# 8-MC_v01.net
KiCad netlist of a schematic drawn in EAGLE
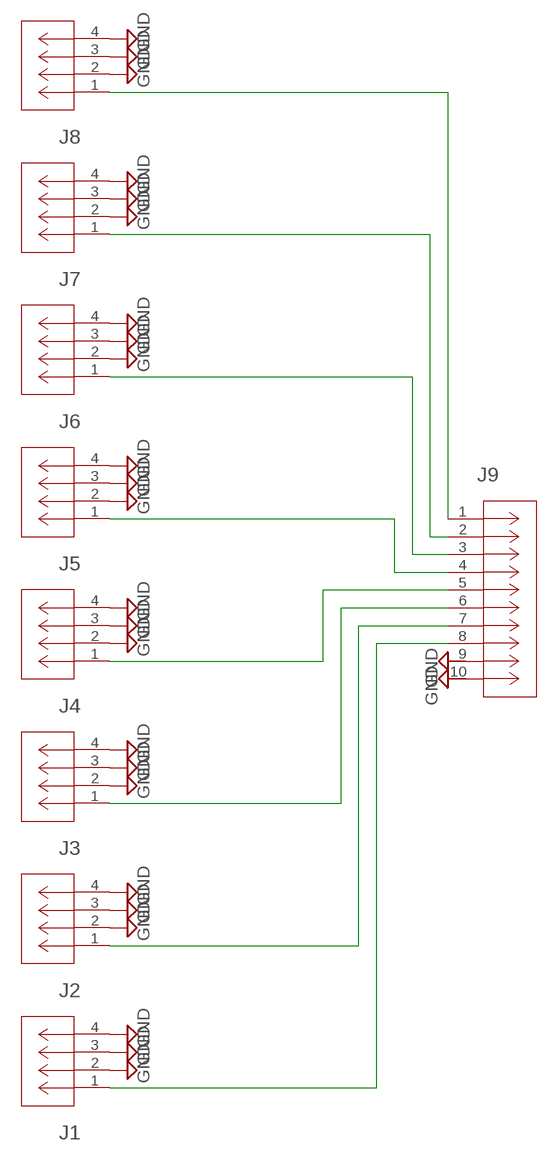
[diagram p0: schematic, sheet 1]

(export (version "E")
  (design (tool "Eeschema 10.0.6"))
  (components
    (comp (ref "J1")
      (value "5055670281CON_5055670281")
      (footprint "eagle-import:CON_5055670281")
      (fields
        (field (name "MANUFACTURER_PART_NUMBER") "5055670281")
        (field (name "COPYRIGHT") "Copyright (C) 2021 Ultra Librarian. All rights reserved.")
      )
      (libsource (lib "eagle-import") (part "5055670281CON_5055670281"))
    )
    (comp (ref "J2")
      (value "5055670281CON_5055670281")
      (footprint "eagle-import:CON_5055670281")
      (fields
        (field (name "MANUFACTURER_PART_NUMBER") "5055670281")
        (field (name "COPYRIGHT") "Copyright (C) 2021 Ultra Librarian. All rights reserved.")
      )
      (libsource (lib "eagle-import") (part "5055670281CON_5055670281"))
    )
    (comp (ref "J3")
      (value "5055670281CON_5055670281")
      (footprint "eagle-import:CON_5055670281")
      (fields
        (field (name "MANUFACTURER_PART_NUMBER") "5055670281")
        (field (name "COPYRIGHT") "Copyright (C) 2021 Ultra Librarian. All rights reserved.")
      )
      (libsource (lib "eagle-import") (part "5055670281CON_5055670281"))
    )
    (comp (ref "J4")
      (value "5055670281CON_5055670281")
      (footprint "eagle-import:CON_5055670281")
      (fields
        (field (name "MANUFACTURER_PART_NUMBER") "5055670281")
        (field (name "COPYRIGHT") "Copyright (C) 2021 Ultra Librarian. All rights reserved.")
      )
      (libsource (lib "eagle-import") (part "5055670281CON_5055670281"))
    )
    (comp (ref "J5")
      (value "5055670281CON_5055670281")
      (footprint "eagle-import:CON_5055670281")
      (fields
        (field (name "MANUFACTURER_PART_NUMBER") "5055670281")
        (field (name "COPYRIGHT") "Copyright (C) 2021 Ultra Librarian. All rights reserved.")
      )
      (libsource (lib "eagle-import") (part "5055670281CON_5055670281"))
    )
    (comp (ref "J6")
      (value "5055670281CON_5055670281")
      (footprint "eagle-import:CON_5055670281")
      (fields
        (field (name "MANUFACTURER_PART_NUMBER") "5055670281")
        (field (name "COPYRIGHT") "Copyright (C) 2021 Ultra Librarian. All rights reserved.")
      )
      (libsource (lib "eagle-import") (part "5055670281CON_5055670281"))
    )
    (comp (ref "J7")
      (value "5055670281CON_5055670281")
      (footprint "eagle-import:CON_5055670281")
      (fields
        (field (name "MANUFACTURER_PART_NUMBER") "5055670281")
        (field (name "COPYRIGHT") "Copyright (C) 2021 Ultra Librarian. All rights reserved.")
      )
      (libsource (lib "eagle-import") (part "5055670281CON_5055670281"))
    )
    (comp (ref "J8")
      (value "5055670281CON_5055670281")
      (footprint "eagle-import:CON_5055670281")
      (fields
        (field (name "MANUFACTURER_PART_NUMBER") "5055670281")
        (field (name "COPYRIGHT") "Copyright (C) 2021 Ultra Librarian. All rights reserved.")
      )
      (libsource (lib "eagle-import") (part "5055670281CON_5055670281"))
    )
    (comp (ref "J9")
      (value "FH52-10S-0.5SHCONN10_FH52-10S-0.5SH_HIR")
      (footprint "eagle-import:CONN10_FH52-10S-0.5SH_HIR")
      (fields
        (field (name "MANUFACTURER_PART_NUMBER") "FH52-10S-0.5SH")
        (field (name "COPYRIGHT") "Copyright (C) 2021 Ultra Librarian. All rights reserved.")
      )
      (libsource (lib "eagle-import") (part "FH52-10S-0.5SHCONN10_FH52-10S-0.5SH_HIR"))
    )
  )
  (nets
    (net (code "1") (name "GND") (class "Default")
      (node (ref "J1") (pin "2") (pinfunction "2_2") (pintype "passive"))
      (node (ref "J1") (pin "3") (pinfunction "3_3") (pintype "passive"))
      (node (ref "J1") (pin "4") (pinfunction "4_4") (pintype "passive"))
      (node (ref "J2") (pin "2") (pinfunction "2_2") (pintype "passive"))
      (node (ref "J2") (pin "3") (pinfunction "3_3") (pintype "passive"))
      (node (ref "J2") (pin "4") (pinfunction "4_4") (pintype "passive"))
      (node (ref "J3") (pin "2") (pinfunction "2_2") (pintype "passive"))
      (node (ref "J3") (pin "3") (pinfunction "3_3") (pintype "passive"))
      (node (ref "J3") (pin "4") (pinfunction "4_4") (pintype "passive"))
      (node (ref "J4") (pin "2") (pinfunction "2_2") (pintype "passive"))
      (node (ref "J4") (pin "3") (pinfunction "3_3") (pintype "passive"))
      (node (ref "J4") (pin "4") (pinfunction "4_4") (pintype "passive"))
      (node (ref "J5") (pin "2") (pinfunction "2_2") (pintype "passive"))
      (node (ref "J5") (pin "3") (pinfunction "3_3") (pintype "passive"))
      (node (ref "J5") (pin "4") (pinfunction "4_4") (pintype "passive"))
      (node (ref "J6") (pin "2") (pinfunction "2_2") (pintype "passive"))
      (node (ref "J6") (pin "3") (pinfunction "3_3") (pintype "passive"))
      (node (ref "J6") (pin "4") (pinfunction "4_4") (pintype "passive"))
      (node (ref "J7") (pin "2") (pinfunction "2_2") (pintype "passive"))
      (node (ref "J7") (pin "3") (pinfunction "3_3") (pintype "passive"))
      (node (ref "J7") (pin "4") (pinfunction "4_4") (pintype "passive"))
      (node (ref "J8") (pin "2") (pinfunction "2_2") (pintype "passive"))
      (node (ref "J8") (pin "3") (pinfunction "3_3") (pintype "passive"))
      (node (ref "J8") (pin "4") (pinfunction "4_4") (pintype "passive"))
    )
    (net (code "2") (name "Net-(J1-Pad1)") (class "Default")
      (node (ref "J1") (pin "1") (pinfunction "1_1") (pintype "passive"))
      (node (ref "J9") (pin "8") (pinfunction "8_8") (pintype "passive"))
    )
    (net (code "3") (name "Net-(J2-Pad1)") (class "Default")
      (node (ref "J2") (pin "1") (pinfunction "1_1") (pintype "passive"))
      (node (ref "J9") (pin "7") (pinfunction "7_7") (pintype "passive"))
    )
    (net (code "4") (name "Net-(J3-Pad1)") (class "Default")
      (node (ref "J3") (pin "1") (pinfunction "1_1") (pintype "passive"))
      (node (ref "J9") (pin "6") (pinfunction "6_6") (pintype "passive"))
    )
    (net (code "5") (name "Net-(J4-Pad1)") (class "Default")
      (node (ref "J4") (pin "1") (pinfunction "1_1") (pintype "passive"))
      (node (ref "J9") (pin "5") (pinfunction "5_5") (pintype "passive"))
    )
    (net (code "6") (name "Net-(J5-Pad1)") (class "Default")
      (node (ref "J5") (pin "1") (pinfunction "1_1") (pintype "passive"))
      (node (ref "J9") (pin "4") (pinfunction "4_4") (pintype "passive"))
    )
    (net (code "7") (name "Net-(J6-Pad1)") (class "Default")
      (node (ref "J6") (pin "1") (pinfunction "1_1") (pintype "passive"))
      (node (ref "J9") (pin "3") (pinfunction "3_3") (pintype "passive"))
    )
    (net (code "8") (name "Net-(J7-Pad1)") (class "Default")
      (node (ref "J7") (pin "1") (pinfunction "1_1") (pintype "passive"))
      (node (ref "J9") (pin "2") (pinfunction "2_2") (pintype "passive"))
    )
    (net (code "9") (name "Net-(J8-Pad1)") (class "Default")
      (node (ref "J8") (pin "1") (pinfunction "1_1") (pintype "passive"))
      (node (ref "J9") (pin "1") (pinfunction "1_1") (pintype "passive"))
    )
    (net (code "10") (name "unconnected-(J9-Pad9)") (class "Default")
      (node (ref "J9") (pin "9") (pinfunction "9_9") (pintype "passive"))
    )
    (net (code "11") (name "unconnected-(J9-Pad10)") (class "Default")
      (node (ref "J9") (pin "10") (pinfunction "10_10") (pintype "passive"))
    )
  )
)
